# CAN.net
KiCad netlist of a schematic drawn in Altium Designer
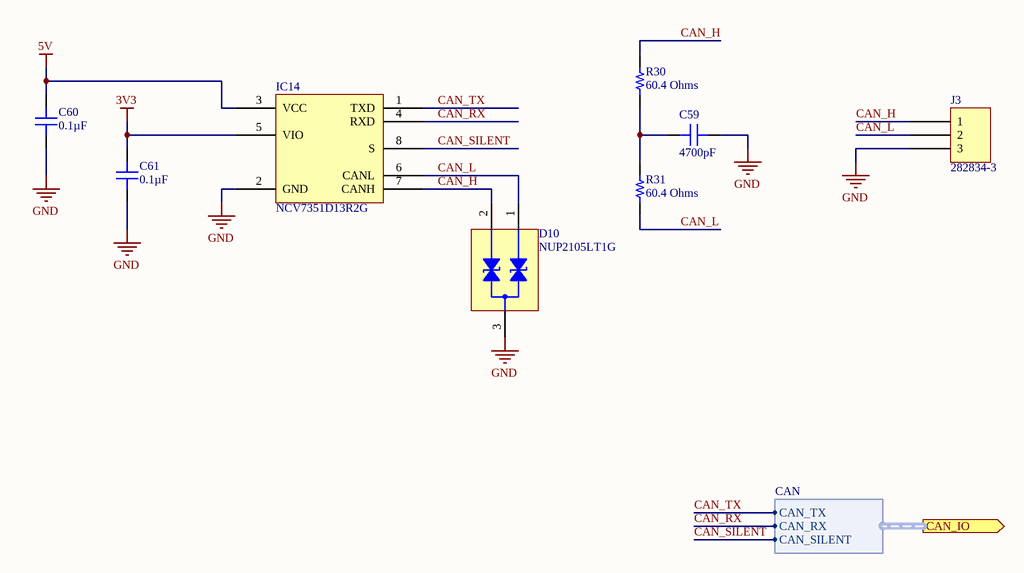
[diagram p0: CAN.SchDoc]

(export (version "E")
  (design (tool "Eeschema 10.0.6"))
  (components
    (comp (ref "C59")
      (value "4700pF")
      (footprint "CAP 0201_0603")
      (description "CAP CER 4700PF 25V X7R 0201")
      (fields
        (field (name "PART NUMBER") "GRM033R71E472KE14D")
        (field (name "MANUFACTURER") "Murata Electronics")
      )
      (libsource (lib "Celestial Altium Library - altium_library") (part "Capacitor"))
    )
    (comp (ref "C60")
      (value "0.1µF")
      (footprint "CAP 0201_0603")
      (description "CAP CER 0.1UF 16V X5R 0201")
      (fields
        (field (name "PART NUMBER") "GRM033R61C104ME84D")
        (field (name "MANUFACTURER") "Murata Electronics")
      )
      (libsource (lib "Celestial Altium Library - altium_library") (part "Capacitor"))
    )
    (comp (ref "C61")
      (value "0.1µF")
      (footprint "CAP 0201_0603")
      (description "CAP CER 0.1UF 16V X5R 0201")
      (fields
        (field (name "PART NUMBER") "GRM033R61C104ME84D")
        (field (name "MANUFACTURER") "Murata Electronics")
      )
      (libsource (lib "Celestial Altium Library - altium_library") (part "Capacitor"))
    )
    (comp (ref "D10")
      (value "NUP2105LT1G")
      (footprint "ON SEMI SOT-23-3")
      (description "TVS DIODE 24V 44V SOT23-3")
      (fields (field (name "MANUFACTURER") "ON Semiconductor"))
      (libsource (lib "Celestial Altium Library - altium_library") (part "ON SEMI SOT-23-3"))
    )
    (comp (ref "IC14")
      (value "NCV7351D13R2G")
      (footprint "ON SEMI - SOIC-8 751AZ")
      (description "IC TRANSCEIVER HALF 1/1 8SOIC")
      (fields (field (name "MANUFACTURER") "ON Semiconductor"))
      (libsource (lib "Celestial Altium Library - altium_library") (part "ON SEMI NCV7351D13R2G"))
    )
    (comp (ref "J3")
      (value "282834-3")
      (footprint "TE 282834-3")
      (description "TERM BLK 3P SIDE ENT 2.54MM PCB")
      (fields (field (name "MANUFACTURER") "TE Connectivity AMP Connectors") (field (name "VOLTAGE") "150V"))
      (libsource (lib "Celestial Altium Library - altium_library") (part "3 Pin"))
    )
    (comp (ref "R30")
      (value "60.4 Ohms")
      (footprint "RES 0201_0603")
      (description "RES SMD 60.4 OHM 1% 1/20W 0201")
      (fields
        (field (name "PART NUMBER") "ERJ-1GNF60R4C")
        (field (name "MANUFACTURER") "Panasonic Electronic Components")
      )
      (libsource (lib "Celestial Altium Library - altium_library") (part "Resistor"))
    )
    (comp (ref "R31")
      (value "60.4 Ohms")
      (footprint "RES 0201_0603")
      (description "RES SMD 60.4 OHM 1% 1/20W 0201")
      (fields
        (field (name "PART NUMBER") "ERJ-1GNF60R4C")
        (field (name "MANUFACTURER") "Panasonic Electronic Components")
      )
      (libsource (lib "Celestial Altium Library - altium_library") (part "Resistor"))
    )
  )
  (nets
    (net (code "2") (name "/CAN_H") (class "Default")
      (node (ref "D10") (pin "2") (pinfunction "GND_2") (pintype "passive"))
      (node (ref "IC14") (pin "7") (pinfunction "CANH_7") (pintype "passive"))
      (node (ref "J3") (pin "1") (pinfunction "1_1") (pintype "passive"))
      (node (ref "R30") (pin "1") (pinfunction "1_1") (pintype "passive"))
    )
    (net (code "3") (name "/CAN_L") (class "Default")
      (node (ref "D10") (pin "1") (pinfunction "I/O_1_1") (pintype "passive"))
      (node (ref "IC14") (pin "6") (pinfunction "CANL_6") (pintype "passive"))
      (node (ref "J3") (pin "2") (pinfunction "2_2") (pintype "passive"))
      (node (ref "R31") (pin "2") (pinfunction "2_2") (pintype "passive"))
    )
    (net (code "4") (name "/CAN_RX") (class "Default")
      (node (ref "IC14") (pin "4") (pinfunction "RXD_4") (pintype "passive"))
    )
    (net (code "5") (name "/CAN_SILENT") (class "Default")
      (node (ref "IC14") (pin "8") (pinfunction "S_8") (pintype "passive"))
    )
    (net (code "6") (name "/CAN_TX") (class "Default")
      (node (ref "IC14") (pin "1") (pinfunction "TXD_1") (pintype "passive"))
    )
    (net (code "8") (name "3V3") (class "Default")
      (node (ref "C61") (pin "2") (pinfunction "2_2") (pintype "passive"))
      (node (ref "IC14") (pin "5") (pinfunction "VIO_5") (pintype "passive"))
    )
    (net (code "9") (name "5V") (class "Default")
      (node (ref "C60") (pin "2") (pinfunction "2_2") (pintype "passive"))
      (node (ref "IC14") (pin "3") (pinfunction "VCC_3") (pintype "passive"))
    )
    (net (code "10") (name "GND") (class "Default")
      (node (ref "C59") (pin "2") (pinfunction "2_2") (pintype "passive"))
      (node (ref "C60") (pin "1") (pinfunction "1_1") (pintype "passive"))
      (node (ref "C61") (pin "1") (pinfunction "1_1") (pintype "passive"))
      (node (ref "D10") (pin "3") (pinfunction "I/O_2_3") (pintype "passive"))
      (node (ref "IC14") (pin "2") (pinfunction "GND_2") (pintype "passive"))
      (node (ref "J3") (pin "3") (pinfunction "3_3") (pintype "passive"))
    )
    (net (code "11") (name "Net-(C59-Pad1)") (class "Default")
      (node (ref "C59") (pin "1") (pinfunction "1_1") (pintype "passive"))
      (node (ref "R30") (pin "2") (pinfunction "2_2") (pintype "passive"))
      (node (ref "R31") (pin "1") (pinfunction "1_1") (pintype "passive"))
    )
  )
)
